# TIDA-PowerNBIoT_Boost.net
KiCad netlist of a schematic drawn in Altium Designer
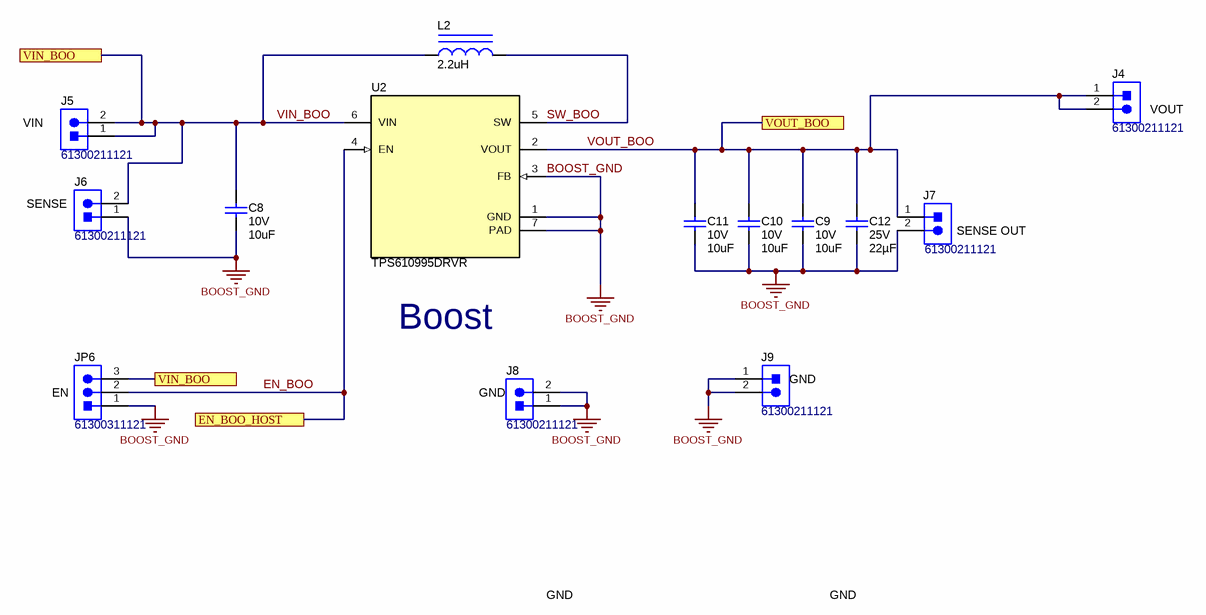
[diagram p0: TIDA-PowerNBIoT_Boost.SchDoc]

(export (version "E")
  (design (tool "Eeschema 10.0.6"))
  (components
    (comp (ref "C8")
      (value "GRM188Z71A106MA73D")
      (footprint "0603")
      (description "CAP, CERM, 10 uF, 10 V, +/- 20%, X7R, 0603")
      (fields
        (field (name "MANUFACTURER") "MuRata")
        (field (name "VDC_V") "10V")
        (field (name "VALUEDISPLAYED") "10uF")
        (field (name "PUBLISHER") "Texas Instruments")
      )
      (libsource (lib "Altium Vault - TI") (part "CMP-0007497-5"))
    )
    (comp (ref "C9")
      (value "GRM188Z71A106MA73D")
      (footprint "0603")
      (description "CAP, CERM, 10 uF, 10 V, +/- 20%, X7R, 0603")
      (fields
        (field (name "MANUFACTURER") "MuRata")
        (field (name "VDC_V") "10V")
        (field (name "VALUEDISPLAYED") "10uF")
        (field (name "PUBLISHER") "Texas Instruments")
      )
      (libsource (lib "Altium Vault - TI") (part "CMP-0007497-5"))
    )
    (comp (ref "C10")
      (value "GRM188Z71A106MA73D")
      (footprint "0603")
      (description "CAP, CERM, 10 uF, 10 V, +/- 20%, X7R, 0603")
      (fields
        (field (name "MANUFACTURER") "MuRata")
        (field (name "VDC_V") "10V")
        (field (name "VALUEDISPLAYED") "10uF")
        (field (name "PUBLISHER") "Texas Instruments")
      )
      (libsource (lib "Altium Vault - TI") (part "CMP-0007497-5"))
    )
    (comp (ref "C11")
      (value "GRM188Z71A106MA73D")
      (footprint "0603")
      (description "CAP, CERM, 10 uF, 10 V, +/- 20%, X7R, 0603")
      (fields
        (field (name "MANUFACTURER") "MuRata")
        (field (name "VDC_V") "10V")
        (field (name "VALUEDISPLAYED") "10uF")
        (field (name "PUBLISHER") "Texas Instruments")
      )
      (libsource (lib "Altium Vault - TI") (part "CMP-0007497-5"))
    )
    (comp (ref "C12")
      (value "TMK212B7225KG-TR")
      (footprint "0805_HV")
      (description "CAP, CERM, 22 µF, 25 V,+/- 10%, X7R, 0805")
      (fields
        (field (name "MANUFACTURER") "Taiyo Yuden")
        (field (name "VDC_V") "25V")
        (field (name "VALUEDISPLAYED") "22µF")
      )
      (libsource (lib "Altium Vault - TI") (part "CMP-0080705-1"))
    )
    (comp (ref "J4")
      (value "61300211121")
      (footprint "WURTH_61300211121")
      (description "Header, 2.54 mm, 2x1, Gold, TH")
      (fields (field (name "MANUFACTURER") "Wurth Elektronik"))
      (libsource (lib "Altium Vault - TI") (part "Header_2x1"))
    )
    (comp (ref "J5")
      (value "61300211121")
      (footprint "WURTH_61300211121")
      (description "Header, 2.54 mm, 2x1, Gold, TH")
      (fields (field (name "MANUFACTURER") "Wurth Elektronik"))
      (libsource (lib "") (part "Header_2x1_1"))
    )
    (comp (ref "J6")
      (value "61300211121")
      (footprint "WURTH_61300211121")
      (description "Header, 2.54 mm, 2x1, Gold, TH")
      (fields (field (name "MANUFACTURER") "Wurth Elektronik"))
      (libsource (lib "") (part "Header_2x1_1"))
    )
    (comp (ref "J7")
      (value "61300211121")
      (footprint "WURTH_61300211121")
      (description "Header, 2.54 mm, 2x1, Gold, TH")
      (fields (field (name "MANUFACTURER") "Wurth Elektronik"))
      (libsource (lib "Altium Vault - TI") (part "Header_2x1"))
    )
    (comp (ref "J8")
      (value "61300211121")
      (footprint "WURTH_61300211121")
      (description "Header, 2.54 mm, 2x1, Gold, TH")
      (fields (field (name "MANUFACTURER") "Wurth Elektronik"))
      (libsource (lib "") (part "Header_2x1_1"))
    )
    (comp (ref "J9")
      (value "61300211121")
      (footprint "WURTH_61300211121")
      (description "Header, 2.54 mm, 2x1, Gold, TH")
      (fields (field (name "MANUFACTURER") "Wurth Elektronik"))
      (libsource (lib "Altium Vault - TI") (part "Header_2x1"))
    )
    (comp (ref "JP6")
      (value "61300311121")
      (footprint "WURTH_61300311121")
      (description "Header, 2.54 mm, 3x1, Gold, TH")
      (fields (field (name "MANUFACTURER") "Wurth Elektronik"))
      (libsource (lib "Altium Vault - TI") (part "Header_3x1"))
    )
    (comp (ref "L2")
      (value "74404024022")
      (footprint "WE_LQS_252012")
      (description "Inductor, Wirewound, Ferrite, 2.2 uH, 1.8 A, 0.08 ohm, SMD")
      (fields
        (field (name "MANUFACTURER") "Wurth Elektronik")
        (field (name "VALUEDISPLAYED") "2.2uH")
        (field (name "PUBLISHER") "Texas Instruments")
      )
      (libsource (lib "Altium Vault - TI") (part "Inductor_Iron"))
    )
    (comp (ref "U2")
      (value "TPS610995DRVR")
      (footprint "DRV0006A")
      (description "Synchronous Boost Converter with 800 nA Ultra-Low Quiescent Current, DRV0006A (WSON-6)")
      (fields
        (field (name "ALTERNATE PARTNUMBER") "TPS610995DRVT")
        (field (name "MANUFACTURER") "Texas Instruments")
        (field (name "PARTNUMBER") "TPS610995DRVR")
      )
      (libsource (lib "Altium Vault - TI") (part "TPS61099"))
    )
  )
  (nets
    (net (code "1") (name "/EN_BOO") (class "Default")
      (node (ref "JP6") (pin "2") (pinfunction "2_2") (pintype "passive"))
      (node (ref "U2") (pin "4") (pinfunction "EN_4") (pintype "input"))
    )
    (net (code "2") (name "/SW_BOO") (class "Default")
      (node (ref "L2") (pin "2") (pinfunction "2_2") (pintype "passive"))
      (node (ref "U2") (pin "5") (pinfunction "SW_5") (pintype "power_in"))
    )
    (net (code "3") (name "/VIN_BOO") (class "Default")
      (node (ref "C8") (pin "1") (pinfunction "1_1") (pintype "passive"))
      (node (ref "J5") (pin "1") (pinfunction "1_1") (pintype "passive"))
      (node (ref "J5") (pin "2") (pinfunction "2_2") (pintype "passive"))
      (node (ref "J6") (pin "2") (pinfunction "2_2") (pintype "passive"))
      (node (ref "JP6") (pin "3") (pinfunction "3_3") (pintype "passive"))
      (node (ref "L2") (pin "1") (pinfunction "1_1") (pintype "passive"))
      (node (ref "U2") (pin "6") (pinfunction "VIN_6") (pintype "power_in"))
    )
    (net (code "4") (name "/VOUT_BOO") (class "Default")
      (node (ref "C10") (pin "1") (pinfunction "1_1") (pintype "passive"))
      (node (ref "C11") (pin "1") (pinfunction "1_1") (pintype "passive"))
      (node (ref "C12") (pin "1") (pinfunction "1_1") (pintype "passive"))
      (node (ref "C9") (pin "1") (pinfunction "1_1") (pintype "passive"))
      (node (ref "J4") (pin "1") (pinfunction "1_1") (pintype "passive"))
      (node (ref "J4") (pin "2") (pinfunction "2_2") (pintype "passive"))
      (node (ref "J7") (pin "1") (pinfunction "1_1") (pintype "passive"))
      (node (ref "U2") (pin "2") (pinfunction "VOUT_2") (pintype "power_in"))
    )
    (net (code "5") (name "BOOST_GND") (class "Default")
      (node (ref "C10") (pin "2") (pinfunction "2_2") (pintype "passive"))
      (node (ref "C11") (pin "2") (pinfunction "2_2") (pintype "passive"))
      (node (ref "C12") (pin "2") (pinfunction "2_2") (pintype "passive"))
      (node (ref "C8") (pin "2") (pinfunction "2_2") (pintype "passive"))
      (node (ref "C9") (pin "2") (pinfunction "2_2") (pintype "passive"))
      (node (ref "J6") (pin "1") (pinfunction "1_1") (pintype "passive"))
      (node (ref "J7") (pin "2") (pinfunction "2_2") (pintype "passive"))
      (node (ref "J8") (pin "1") (pinfunction "1_1") (pintype "passive"))
      (node (ref "J8") (pin "2") (pinfunction "2_2") (pintype "passive"))
      (node (ref "J9") (pin "1") (pinfunction "1_1") (pintype "passive"))
      (node (ref "J9") (pin "2") (pinfunction "2_2") (pintype "passive"))
      (node (ref "JP6") (pin "1") (pinfunction "1_1") (pintype "passive"))
      (node (ref "U2") (pin "1") (pinfunction "GND_1") (pintype "power_in"))
      (node (ref "U2") (pin "3") (pinfunction "FB_3") (pintype "input"))
      (node (ref "U2") (pin "7") (pinfunction "PAD_7") (pintype "power_in"))
    )
  )
)
